# 01_VS1053.net
KiCad netlist of a schematic drawn in Altium Designer
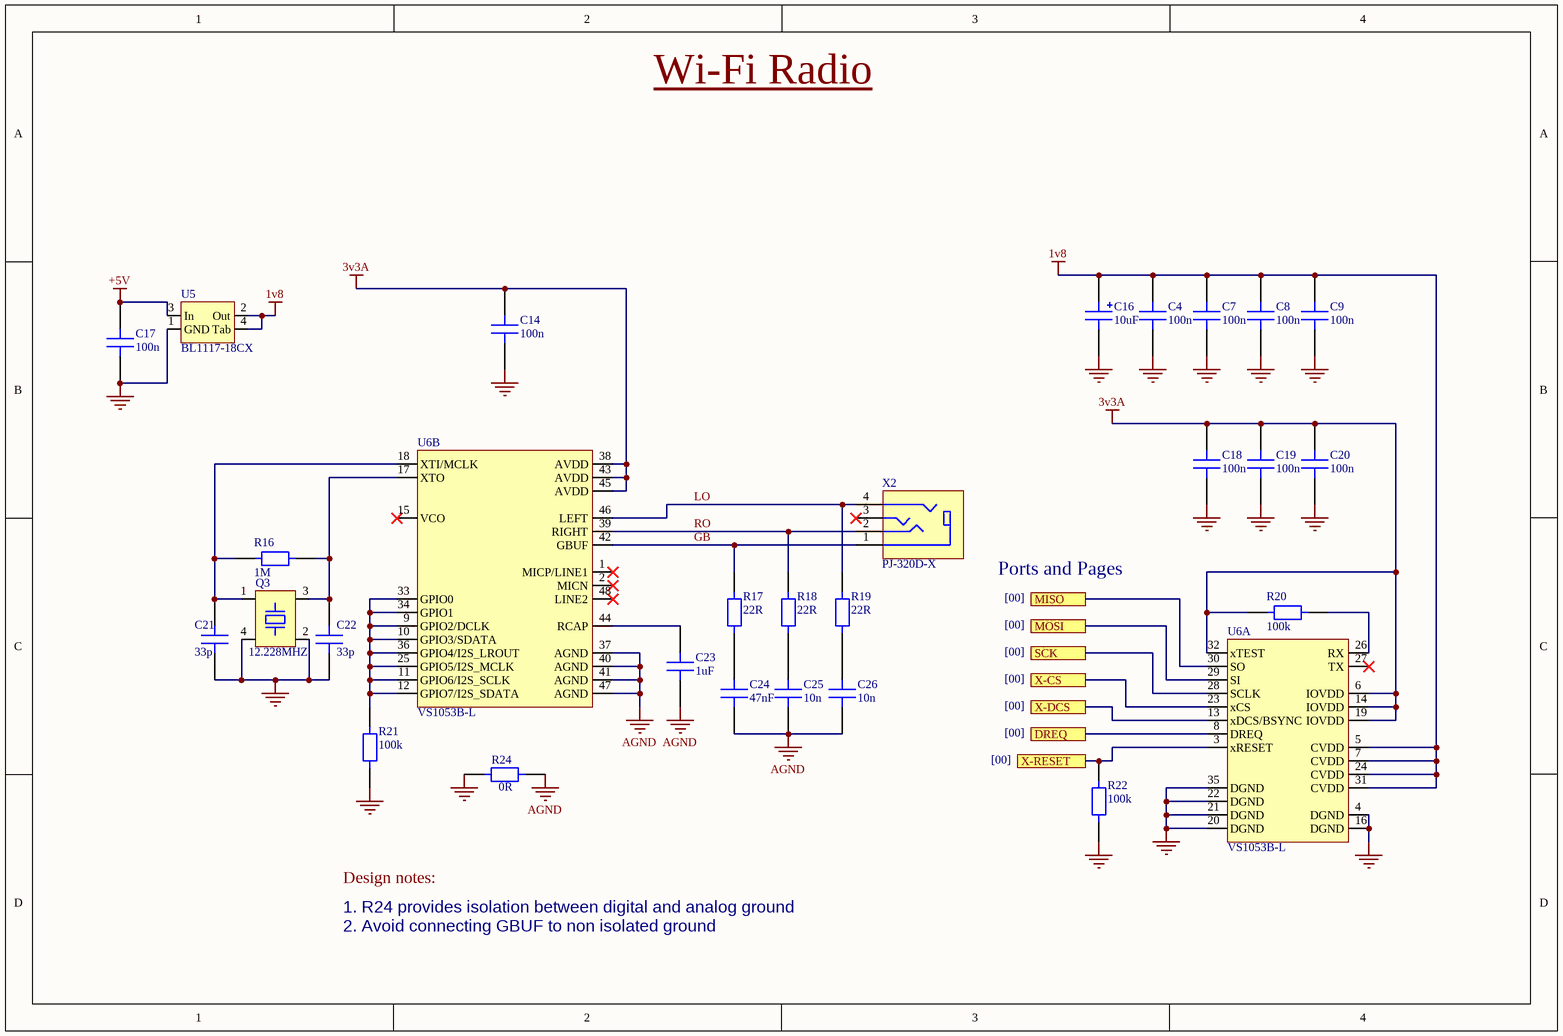
[diagram p0: [01] VS1053.SchDoc]

(export (version "E")
  (design (tool "Eeschema 10.0.6"))
  (components
    (comp (ref "C4")
      (value "100n")
      (footprint "0603 CAP")
      (description "MULTILAYER CERAMIC CAPACITORS MLCC - SMD/SMT 100NF 50V 0603 ROHS")
      (fields (field (name "MANUFACTURER") "YAGEO") (field (name "MFR.PART #") "CC0603KRX7R9BB104"))
      (libsource (lib "JLC_Lib") (part "CC0603KRX7R9BB104"))
    )
    (comp (ref "C7")
      (value "100n")
      (footprint "0603 CAP")
      (description "MULTILAYER CERAMIC CAPACITORS MLCC - SMD/SMT 100NF 50V 0603 ROHS")
      (fields (field (name "MANUFACTURER") "YAGEO") (field (name "MFR.PART #") "CC0603KRX7R9BB104"))
      (libsource (lib "JLC_Lib") (part "CC0603KRX7R9BB104"))
    )
    (comp (ref "C8")
      (value "100n")
      (footprint "0603 CAP")
      (description "MULTILAYER CERAMIC CAPACITORS MLCC - SMD/SMT 100NF 50V 0603 ROHS")
      (fields (field (name "MANUFACTURER") "YAGEO") (field (name "MFR.PART #") "CC0603KRX7R9BB104"))
      (libsource (lib "JLC_Lib") (part "CC0603KRX7R9BB104"))
    )
    (comp (ref "C9")
      (value "100n")
      (footprint "0603 CAP")
      (description "MULTILAYER CERAMIC CAPACITORS MLCC - SMD/SMT 100NF 50V 0603 ROHS")
      (fields (field (name "MANUFACTURER") "YAGEO") (field (name "MFR.PART #") "CC0603KRX7R9BB104"))
      (libsource (lib "JLC_Lib") (part "CC0603KRX7R9BB104"))
    )
    (comp (ref "C14")
      (value "100n")
      (footprint "0603 CAP")
      (description "MULTILAYER CERAMIC CAPACITORS MLCC - SMD/SMT 100NF 50V 0603 ROHS")
      (fields (field (name "MANUFACTURER") "YAGEO") (field (name "MFR.PART #") "CC0603KRX7R9BB104"))
      (libsource (lib "JLC_Lib") (part "CC0603KRX7R9BB104"))
    )
    (comp (ref "C16")
      (value "10uF")
      (footprint "CAP 1206")
      (description "TANTALUM CAPACITORS 10UF 16V CASE-A_3216 ROHS")
      (fields (field (name "MANUFACTURER") "AVX") (field (name "MFR.PART #") "TAJA106K016RNJ"))
      (libsource (lib "JLC_Lib") (part "TAJA106K016RNJ"))
    )
    (comp (ref "C17")
      (value "100n")
      (footprint "0603 CAP")
      (description "MULTILAYER CERAMIC CAPACITORS MLCC - SMD/SMT 100NF 50V 0603 ROHS")
      (fields (field (name "MANUFACTURER") "YAGEO") (field (name "MFR.PART #") "CC0603KRX7R9BB104"))
      (libsource (lib "JLC_Lib") (part "CC0603KRX7R9BB104"))
    )
    (comp (ref "C18")
      (value "100n")
      (footprint "0603 CAP")
      (description "MULTILAYER CERAMIC CAPACITORS MLCC - SMD/SMT 100NF 50V 0603 ROHS")
      (fields (field (name "MANUFACTURER") "YAGEO") (field (name "MFR.PART #") "CC0603KRX7R9BB104"))
      (libsource (lib "JLC_Lib") (part "CC0603KRX7R9BB104"))
    )
    (comp (ref "C19")
      (value "100n")
      (footprint "0603 CAP")
      (description "MULTILAYER CERAMIC CAPACITORS MLCC - SMD/SMT 100NF 50V 0603 ROHS")
      (fields (field (name "MANUFACTURER") "YAGEO") (field (name "MFR.PART #") "CC0603KRX7R9BB104"))
      (libsource (lib "JLC_Lib") (part "CC0603KRX7R9BB104"))
    )
    (comp (ref "C20")
      (value "100n")
      (footprint "0603 CAP")
      (description "MULTILAYER CERAMIC CAPACITORS MLCC - SMD/SMT 100NF 50V 0603 ROHS")
      (fields (field (name "MANUFACTURER") "YAGEO") (field (name "MFR.PART #") "CC0603KRX7R9BB104"))
      (libsource (lib "JLC_Lib") (part "CC0603KRX7R9BB104"))
    )
    (comp (ref "C21")
      (value "33p")
      (footprint "0603 CAP")
      (description "MULTILAYER CERAMIC CAPACITORS MLCC - SMD/SMT 33PF 50V 0603 ROHS")
      (fields
        (field (name "MANUFACTURER") "Samsung Electro-Mechanics")
        (field (name "MFR.PART #") "CL10C330JB8NNNC")
      )
      (libsource (lib "JLC_Lib") (part "CL10C330JB8NNNC"))
    )
    (comp (ref "C22")
      (value "33p")
      (footprint "0603 CAP")
      (description "MULTILAYER CERAMIC CAPACITORS MLCC - SMD/SMT 33PF 50V 0603 ROHS")
      (fields
        (field (name "MANUFACTURER") "Samsung Electro-Mechanics")
        (field (name "MFR.PART #") "CL10C330JB8NNNC")
      )
      (libsource (lib "JLC_Lib") (part "CL10C330JB8NNNC"))
    )
    (comp (ref "C23")
      (value "1uF")
      (footprint "0603 CAP")
      (description "MULTILAYER CERAMIC CAPACITORS MLCC - SMD/SMT 1UF 50V 0603 ROHS")
      (fields
        (field (name "MANUFACTURER") "Samsung Electro-Mechanics")
        (field (name "MFR.PART #") "CL10A105KB8NNNC")
      )
      (libsource (lib "JLC_Lib") (part "CL10A105KB8NNNC"))
    )
    (comp (ref "C24")
      (value "47nF")
      (footprint "0603 CAP")
      (description "MULTILAYER CERAMIC CAPACITORS MLCC - SMD/SMT 47NF 50V 0603 ROHS")
      (fields
        (field (name "MANUFACTURER") "Samsung Electro-Mechanics")
        (field (name "MFR.PART #") "CL10B473KB8NNNC")
      )
      (libsource (lib "JLC_Lib") (part "CL10B473KB8NNNC"))
    )
    (comp (ref "C25")
      (value "10n")
      (footprint "0603 CAP")
      (description "MULTILAYER CERAMIC CAPACITORS MLCC - SMD/SMT 10NF 50V 0603 ROHS")
      (fields
        (field (name "MANUFACTURER") "Guangdong Fenghua Advanced Tech")
        (field (name "MFR.PART #") "0603B103K500NT")
      )
      (libsource (lib "JLC_Lib") (part "0603B103K500NT"))
    )
    (comp (ref "C26")
      (value "10n")
      (footprint "0603 CAP")
      (description "MULTILAYER CERAMIC CAPACITORS MLCC - SMD/SMT 10NF 50V 0603 ROHS")
      (fields
        (field (name "MANUFACTURER") "Guangdong Fenghua Advanced Tech")
        (field (name "MFR.PART #") "0603B103K500NT")
      )
      (libsource (lib "JLC_Lib") (part "0603B103K500NT"))
    )
    (comp (ref "Q3")
      (value "12.228MHZ")
      (footprint "ABM8W")
      (description "SMD CRYSTAL RESONATORS 12.288MHZ ±10PPM SMD-3225_4P ROHS")
      (fields (field (name "MANUFACTURER") "Yangxing Tech") (field (name "MFR.PART #") "X322512288MOB4SC"))
      (libsource (lib "JLC_Lib") (part "X322512288MOB4SC"))
    )
    (comp (ref "R16")
      (value "1M")
      (footprint "0603 RES")
      (description "CHIP RESISTOR - SURFACE MOUNT 1MOHMS ±1% 1/10W 0603 ROHS")
      (fields (field (name "MANUFACTURER") "Uniroyal Elec") (field (name "MFR.PART #") "0603WAF1004T5E"))
      (libsource (lib "JLC_Lib") (part "0603WAF1004T5E"))
    )
    (comp (ref "R17")
      (value "22R")
      (footprint "0603 RES")
      (description "CHIP RESISTOR - SURFACE MOUNT 22OHMS ±1% 1/10W 0603 ROHS")
      (fields (field (name "MANUFACTURER") "Uniroyal Elec") (field (name "MFR.PART #") "0603WAF220JT5E"))
      (libsource (lib "JLC_Lib") (part "0603WAF220JT5E"))
    )
    (comp (ref "R18")
      (value "22R")
      (footprint "0603 RES")
      (description "CHIP RESISTOR - SURFACE MOUNT 22OHMS ±1% 1/10W 0603 ROHS")
      (fields (field (name "MANUFACTURER") "Uniroyal Elec") (field (name "MFR.PART #") "0603WAF220JT5E"))
      (libsource (lib "JLC_Lib") (part "0603WAF220JT5E"))
    )
    (comp (ref "R19")
      (value "22R")
      (footprint "0603 RES")
      (description "CHIP RESISTOR - SURFACE MOUNT 22OHMS ±1% 1/10W 0603 ROHS")
      (fields (field (name "MANUFACTURER") "Uniroyal Elec") (field (name "MFR.PART #") "0603WAF220JT5E"))
      (libsource (lib "JLC_Lib") (part "0603WAF220JT5E"))
    )
    (comp (ref "R20")
      (value "100k")
      (footprint "0603 RES")
      (description "CHIP RESISTOR - SURFACE MOUNT 100KOHMS ±1% 1/10W 0603 ROHS")
      (fields (field (name "MANUFACTURER") "Uniroyal Elec") (field (name "MFR.PART #") "0603WAF1003T5E"))
      (libsource (lib "JLC_Lib") (part "0603WAF1003T5E"))
    )
    (comp (ref "R21")
      (value "100k")
      (footprint "0603 RES")
      (description "CHIP RESISTOR - SURFACE MOUNT 100KOHMS ±1% 1/10W 0603 ROHS")
      (fields (field (name "MANUFACTURER") "Uniroyal Elec") (field (name "MFR.PART #") "0603WAF1003T5E"))
      (libsource (lib "JLC_Lib") (part "0603WAF1003T5E"))
    )
    (comp (ref "R22")
      (value "100k")
      (footprint "0603 RES")
      (description "CHIP RESISTOR - SURFACE MOUNT 100KOHMS ±1% 1/10W 0603 ROHS")
      (fields (field (name "MANUFACTURER") "Uniroyal Elec") (field (name "MFR.PART #") "0603WAF1003T5E"))
      (libsource (lib "JLC_Lib") (part "0603WAF1003T5E"))
    )
    (comp (ref "R24")
      (value "0R")
      (footprint "0603 RES")
      (description "CHIP RESISTOR - SURFACE MOUNT 0OHMS ±1% 1/10W 0603 ROHS")
      (fields (field (name "MANUFACTURER") "Uniroyal Elec") (field (name "MFR.PART #") "0603WAF0000T5E"))
      (libsource (lib "JLC_Lib") (part "0603WAF0000T5E"))
    )
    (comp (ref "U5")
      (value "BL1117-18CX")
      (footprint "SOT233-3")
      (description "LOW DROPOUT REGULATORS(LDO) POSITIVE FIXED 1.5V @ 1A 12V 1.8V 1A SOT-223 ROHS")
      (fields (field (name "MANUFACTURER") "Shanghai Belling") (field (name "LCSC PART #") "C78971"))
      (libsource (lib "JLC_Lib") (part "BL1117-18CX"))
    )
    (comp (ref "U6")
      (value "VS1053B-L")
      (footprint "LQFP-48")
      (description "VIDEO-AUDIO INTERFACE ICS LQFP-48_7X7X05P ROHS")
      (fields (field (name "MANUFACTURER") "VLSI Solution") (field (name "LCSC PART #") "C9922"))
      (libsource (lib "JLC_Lib") (part "VS1053B-L"))
    )
    (comp (ref "X2")
      (value "PJ-320D-X")
      (footprint "3.5mm Jack")
      (description "3.5mm SMD Headphone Holder 4 Female Horizontal SMD Audio & Video Connectors RoHS")
      (fields (field (name "MANUFACTURER") "XKB Enterprise") (field (name "LCSC PART #") "C319111"))
      (libsource (lib "JLC_Lib") (part "PJ-320D-X"))
    )
  )
  (nets
    (net (code "1") (name "+5V") (class "Default")
      (node (ref "C17") (pin "2") (pinfunction "2_2") (pintype "passive"))
      (node (ref "U5") (pin "3") (pinfunction "In_3") (pintype "passive"))
    )
    (net (code "2") (name "/DREQ") (class "Default")
      (node (ref "U6") (pin "8") (pinfunction "DREQ_8") (pintype "passive"))
    )
    (net (code "3") (name "/GB") (class "Default")
      (node (ref "R17") (pin "2") (pinfunction "2_2") (pintype "passive"))
      (node (ref "U6") (pin "42") (pinfunction "GBUF_42") (pintype "passive"))
      (node (ref "X2") (pin "1") (pinfunction "1_1") (pintype "passive"))
    )
    (net (code "4") (name "/LO") (class "Default")
      (node (ref "R19") (pin "2") (pinfunction "2_2") (pintype "passive"))
      (node (ref "U6") (pin "46") (pinfunction "LEFT_46") (pintype "passive"))
      (node (ref "X2") (pin "4") (pinfunction "4_4") (pintype "passive"))
    )
    (net (code "5") (name "/MISO") (class "Default")
      (node (ref "U6") (pin "30") (pinfunction "SO_30") (pintype "passive"))
    )
    (net (code "6") (name "/MOSI") (class "Default")
      (node (ref "U6") (pin "29") (pinfunction "SI_29") (pintype "passive"))
    )
    (net (code "7") (name "/RO") (class "Default")
      (node (ref "R18") (pin "2") (pinfunction "2_2") (pintype "passive"))
      (node (ref "U6") (pin "39") (pinfunction "RIGHT_39") (pintype "passive"))
      (node (ref "X2") (pin "2") (pinfunction "2_2") (pintype "passive"))
    )
    (net (code "8") (name "/SCK") (class "Default")
      (node (ref "U6") (pin "28") (pinfunction "SCLK_28") (pintype "passive"))
    )
    (net (code "9") (name "/X-CS") (class "Default")
      (node (ref "U6") (pin "23") (pinfunction "xCS_23") (pintype "passive"))
    )
    (net (code "10") (name "/X-DCS") (class "Default")
      (node (ref "U6") (pin "13") (pinfunction "xDCS/BSYNC_13") (pintype "passive"))
    )
    (net (code "11") (name "/X-RESET") (class "Default")
      (node (ref "R22") (pin "2") (pinfunction "2_2") (pintype "passive"))
      (node (ref "U6") (pin "3") (pinfunction "xRESET_3") (pintype "passive"))
    )
    (net (code "12") (name "1v8") (class "Default")
      (node (ref "C16") (pin "1") (pinfunction "1_1") (pintype "passive"))
      (node (ref "C4") (pin "2") (pinfunction "2_2") (pintype "passive"))
      (node (ref "C7") (pin "2") (pinfunction "2_2") (pintype "passive"))
      (node (ref "C8") (pin "2") (pinfunction "2_2") (pintype "passive"))
      (node (ref "C9") (pin "2") (pinfunction "2_2") (pintype "passive"))
      (node (ref "U5") (pin "2") (pinfunction "Out_2") (pintype "passive"))
      (node (ref "U5") (pin "4") (pinfunction "Tab_4") (pintype "passive"))
      (node (ref "U6") (pin "24") (pinfunction "CVDD_24") (pintype "passive"))
      (node (ref "U6") (pin "31") (pinfunction "CVDD_31") (pintype "passive"))
      (node (ref "U6") (pin "5") (pinfunction "CVDD_5") (pintype "passive"))
      (node (ref "U6") (pin "7") (pinfunction "CVDD_7") (pintype "passive"))
    )
    (net (code "13") (name "3v3A") (class "Default")
      (node (ref "C14") (pin "2") (pinfunction "2_2") (pintype "passive"))
      (node (ref "C18") (pin "2") (pinfunction "2_2") (pintype "passive"))
      (node (ref "C19") (pin "2") (pinfunction "2_2") (pintype "passive"))
      (node (ref "C20") (pin "2") (pinfunction "2_2") (pintype "passive"))
      (node (ref "R20") (pin "2") (pinfunction "2_2") (pintype "passive"))
      (node (ref "U6") (pin "14") (pinfunction "IOVDD_14") (pintype "passive"))
      (node (ref "U6") (pin "19") (pinfunction "IOVDD_19") (pintype "passive"))
      (node (ref "U6") (pin "32") (pinfunction "xTEST_32") (pintype "passive"))
      (node (ref "U6") (pin "38") (pinfunction "AVDD_38") (pintype "passive"))
      (node (ref "U6") (pin "43") (pinfunction "AVDD_43") (pintype "passive"))
      (node (ref "U6") (pin "45") (pinfunction "AVDD_45") (pintype "passive"))
      (node (ref "U6") (pin "6") (pinfunction "IOVDD_6") (pintype "passive"))
    )
    (net (code "14") (name "AGND") (class "Default")
      (node (ref "C23") (pin "1") (pinfunction "1_1") (pintype "passive"))
      (node (ref "C24") (pin "1") (pinfunction "1_1") (pintype "passive"))
      (node (ref "C25") (pin "1") (pinfunction "1_1") (pintype "passive"))
      (node (ref "C26") (pin "1") (pinfunction "1_1") (pintype "passive"))
      (node (ref "R24") (pin "2") (pinfunction "2_2") (pintype "passive"))
      (node (ref "U6") (pin "37") (pinfunction "AGND_37") (pintype "passive"))
      (node (ref "U6") (pin "40") (pinfunction "AGND_40") (pintype "passive"))
      (node (ref "U6") (pin "41") (pinfunction "AGND_41") (pintype "passive"))
      (node (ref "U6") (pin "47") (pinfunction "AGND_47") (pintype "passive"))
    )
    (net (code "15") (name "GND") (class "Default")
      (node (ref "C14") (pin "1") (pinfunction "1_1") (pintype "passive"))
      (node (ref "C16") (pin "2") (pinfunction "2_2") (pintype "passive"))
      (node (ref "C17") (pin "1") (pinfunction "1_1") (pintype "passive"))
      (node (ref "C18") (pin "1") (pinfunction "1_1") (pintype "passive"))
      (node (ref "C19") (pin "1") (pinfunction "1_1") (pintype "passive"))
      (node (ref "C20") (pin "1") (pinfunction "1_1") (pintype "passive"))
      (node (ref "C21") (pin "1") (pinfunction "1_1") (pintype "passive"))
      (node (ref "C22") (pin "1") (pinfunction "1_1") (pintype "passive"))
      (node (ref "C4") (pin "1") (pinfunction "1_1") (pintype "passive"))
      (node (ref "C7") (pin "1") (pinfunction "1_1") (pintype "passive"))
      (node (ref "C8") (pin "1") (pinfunction "1_1") (pintype "passive"))
      (node (ref "C9") (pin "1") (pinfunction "1_1") (pintype "passive"))
      (node (ref "Q3") (pin "2") (pinfunction "GND_2") (pintype "passive"))
      (node (ref "Q3") (pin "4") (pinfunction "GND_4") (pintype "passive"))
      (node (ref "R21") (pin "1") (pinfunction "1_1") (pintype "passive"))
      (node (ref "R22") (pin "1") (pinfunction "1_1") (pintype "passive"))
      (node (ref "R24") (pin "1") (pinfunction "1_1") (pintype "passive"))
      (node (ref "U5") (pin "1") (pinfunction "GND_1") (pintype "passive"))
      (node (ref "U6") (pin "16") (pinfunction "DGND_16") (pintype "passive"))
      (node (ref "U6") (pin "20") (pinfunction "DGND_20") (pintype "passive"))
      (node (ref "U6") (pin "21") (pinfunction "DGND_21") (pintype "passive"))
      (node (ref "U6") (pin "22") (pinfunction "DGND_22") (pintype "passive"))
      (node (ref "U6") (pin "35") (pinfunction "DGND_35") (pintype "passive"))
      (node (ref "U6") (pin "4") (pinfunction "DGND_4") (pintype "passive"))
    )
    (net (code "16") (name "Net-(C24-Pad2)") (class "Default")
      (node (ref "C24") (pin "2") (pinfunction "2_2") (pintype "passive"))
      (node (ref "R17") (pin "1") (pinfunction "1_1") (pintype "passive"))
    )
    (net (code "17") (name "Net-(C25-Pad2)") (class "Default")
      (node (ref "C25") (pin "2") (pinfunction "2_2") (pintype "passive"))
      (node (ref "R18") (pin "1") (pinfunction "1_1") (pintype "passive"))
    )
    (net (code "18") (name "Net-(C26-Pad2)") (class "Default")
      (node (ref "C26") (pin "2") (pinfunction "2_2") (pintype "passive"))
      (node (ref "R19") (pin "1") (pinfunction "1_1") (pintype "passive"))
    )
    (net (code "19") (name "Net-(U6A-RX)") (class "Default")
      (node (ref "R20") (pin "1") (pinfunction "1_1") (pintype "passive"))
      (node (ref "U6") (pin "26") (pinfunction "RX_26") (pintype "passive"))
    )
    (net (code "20") (name "Net-(U6B-GPIO0)") (class "Default")
      (node (ref "R21") (pin "2") (pinfunction "2_2") (pintype "passive"))
      (node (ref "U6") (pin "10") (pinfunction "GPIO3/SDATA_10") (pintype "passive"))
      (node (ref "U6") (pin "11") (pinfunction "GPIO6/I2S_SCLK_11") (pintype "passive"))
      (node (ref "U6") (pin "12") (pinfunction "GPIO7/I2S_SDATA_12") (pintype "passive"))
      (node (ref "U6") (pin "25") (pinfunction "GPIO5/I2S_MCLK_25") (pintype "passive"))
      (node (ref "U6") (pin "33") (pinfunction "GPIO0_33") (pintype "passive"))
      (node (ref "U6") (pin "34") (pinfunction "GPIO1_34") (pintype "passive"))
      (node (ref "U6") (pin "36") (pinfunction "GPIO4/I2S_LROUT_36") (pintype "passive"))
      (node (ref "U6") (pin "9") (pinfunction "GPIO2/DCLK_9") (pintype "passive"))
    )
    (net (code "21") (name "Net-(U6B-RCAP)") (class "Default")
      (node (ref "C23") (pin "2") (pinfunction "2_2") (pintype "passive"))
      (node (ref "U6") (pin "44") (pinfunction "RCAP_44") (pintype "passive"))
    )
    (net (code "22") (name "Net-(U6B-XTI{slash}MCLK)") (class "Default")
      (node (ref "C21") (pin "2") (pinfunction "2_2") (pintype "passive"))
      (node (ref "Q3") (pin "1") (pinfunction "1_1") (pintype "passive"))
      (node (ref "R16") (pin "1") (pinfunction "1_1") (pintype "passive"))
      (node (ref "U6") (pin "18") (pinfunction "XTI/MCLK_18") (pintype "passive"))
    )
    (net (code "23") (name "Net-(U6B-XTO)") (class "Default")
      (node (ref "C22") (pin "2") (pinfunction "2_2") (pintype "passive"))
      (node (ref "Q3") (pin "3") (pinfunction "3_3") (pintype "passive"))
      (node (ref "R16") (pin "2") (pinfunction "2_2") (pintype "passive"))
      (node (ref "U6") (pin "17") (pinfunction "XTO_17") (pintype "passive"))
    )
    (net (code "24") (name "unconnected-(U6A-TX-Pad27)") (class "Default")
      (node (ref "U6") (pin "27") (pinfunction "TX_27") (pintype "passive+no_connect"))
    )
    (net (code "25") (name "unconnected-(U6B-LINE2-Pad48)") (class "Default")
      (node (ref "U6") (pin "48") (pinfunction "LINE2_48") (pintype "passive+no_connect"))
    )
    (net (code "26") (name "unconnected-(U6B-MICN-Pad2)") (class "Default")
      (node (ref "U6") (pin "2") (pinfunction "MICN_2") (pintype "passive+no_connect"))
    )
    (net (code "27") (name "unconnected-(U6B-MICP{slash}LINE1-Pad1)") (class "Default")
      (node (ref "U6") (pin "1") (pinfunction "MICP/LINE1_1") (pintype "passive+no_connect"))
    )
    (net (code "28") (name "unconnected-(U6B-VCO-Pad15)") (class "Default")
      (node (ref "U6") (pin "15") (pinfunction "VCO_15") (pintype "passive+no_connect"))
    )
    (net (code "29") (name "unconnected-(X2-Pad3)") (class "Default")
      (node (ref "X2") (pin "3") (pinfunction "3_3") (pintype "passive+no_connect"))
    )
  )
)
